# SingleCtrl.net
KiCad netlist of a schematic drawn in EAGLE
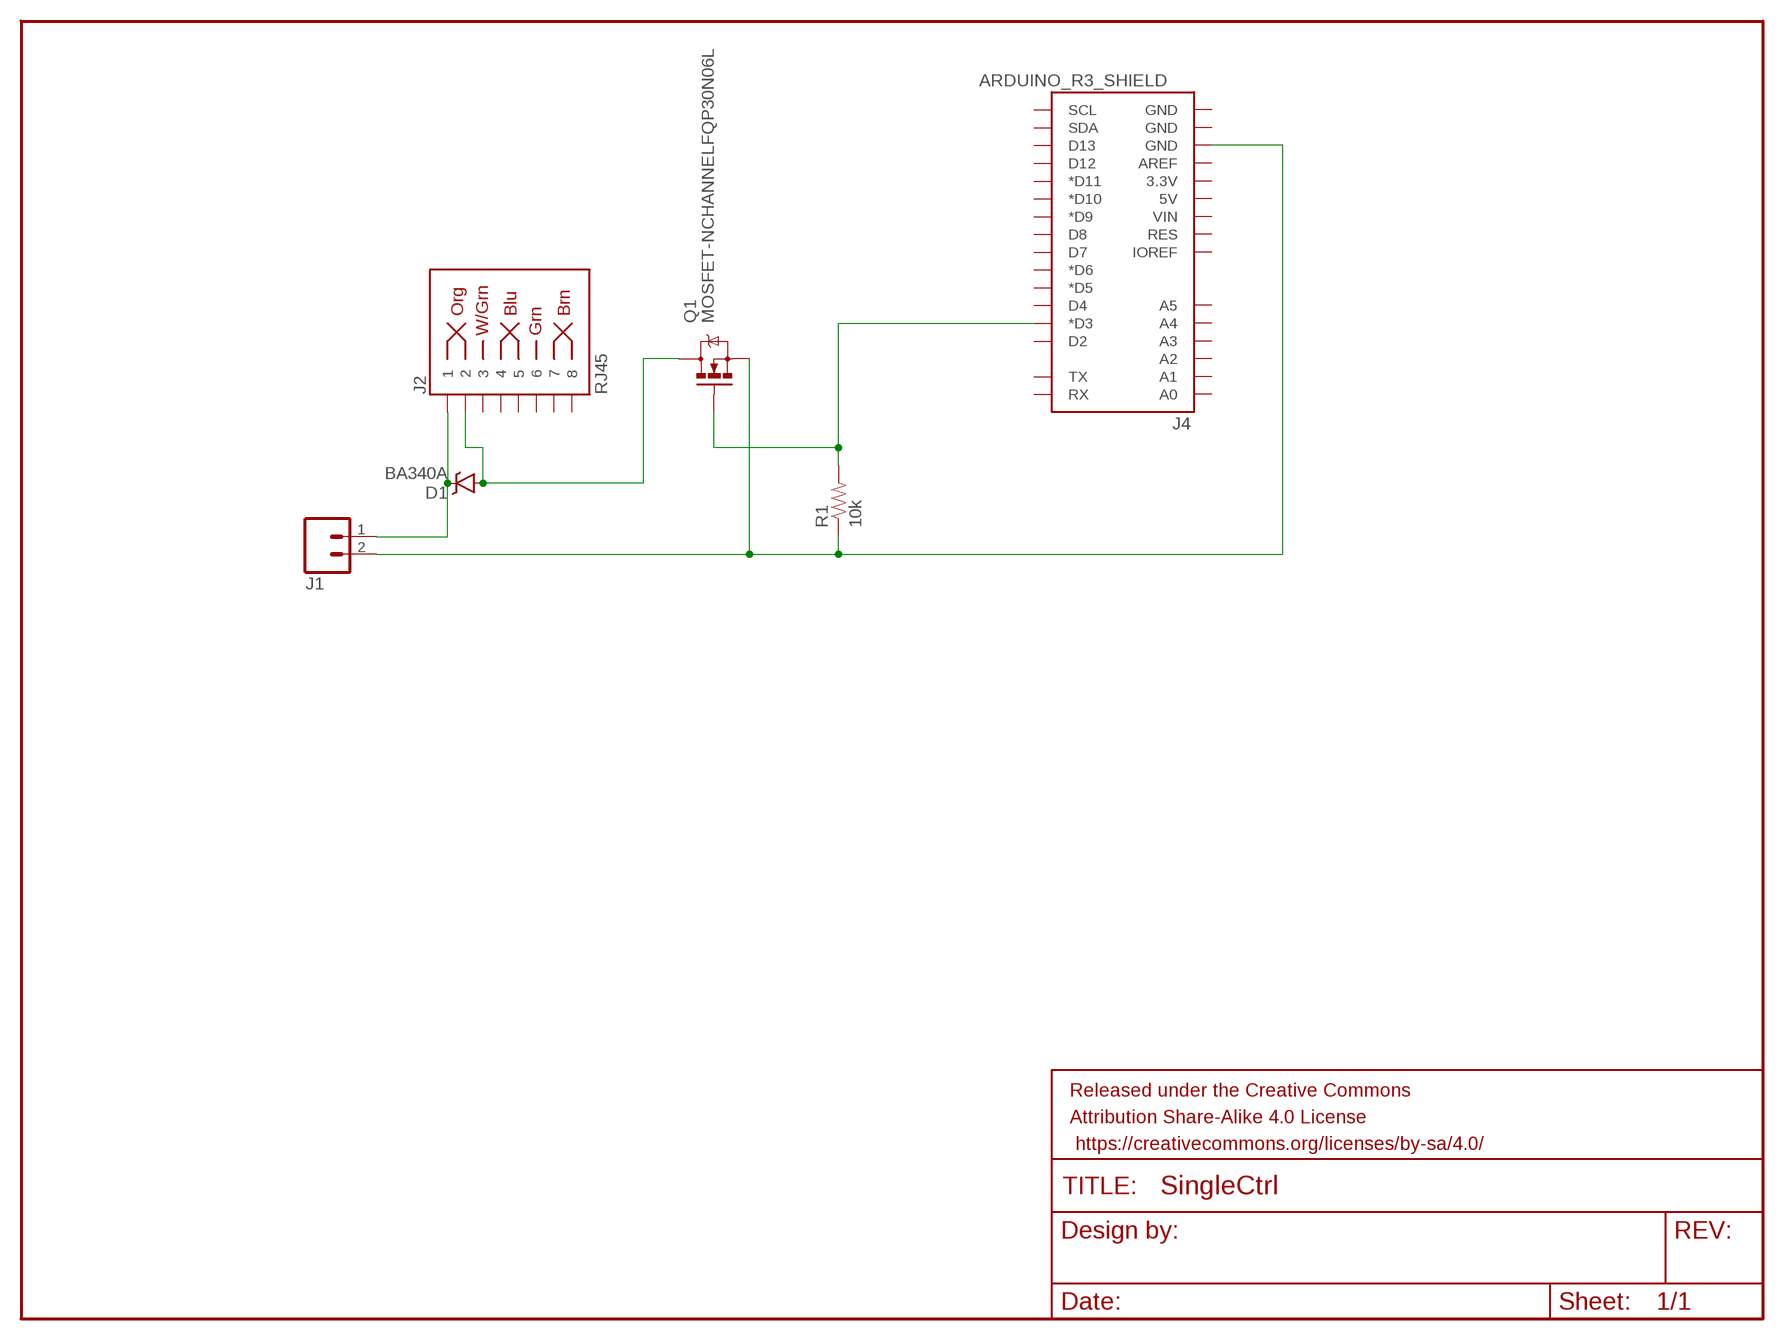
[diagram p0: schematic, sheet 1]

(export (version "E")
  (design (tool "Eeschema 10.0.6"))
  (components
    (comp (ref "D1")
      (value "BA340A")
      (footprint "eagle-import:SMA-DIODE")
      (libsource (lib "eagle-import") (part "B340A"))
    )
    (comp (ref "FRAME1")
      (value "FRAME-LETTER")
      (footprint "eagle-import:CREATIVE_COMMONS")
      (libsource (lib "eagle-import") (part "FRAME-LETTER"))
    )
    (comp (ref "J1")
      (value "M02JST-PTH-2")
      (footprint "eagle-import:JST-2-PTH")
      (libsource (lib "eagle-import") (part "M02JST-PTH-2"))
    )
    (comp (ref "J2")
      (value "RJ45")
      (footprint "eagle-import:RJ45-8")
      (libsource (lib "eagle-import") (part "RJ45-8PTH"))
    )
    (comp (ref "J4")
      (value "ARDUINO_R3_SHIELD")
      (footprint "eagle-import:UNO_R3_SHIELD")
      (libsource (lib "eagle-import") (part "ARDUINO_R3_SHIELD"))
    )
    (comp (ref "Q1")
      (value "MOSFET-NCHANNELFQP30N06L")
      (footprint "eagle-import:TO220V")
      (libsource (lib "eagle-import") (part "MOSFET-NCHANNELFQP30N06L"))
    )
    (comp (ref "R1")
      (value "10k")
      (footprint "eagle-import:AXIAL-0.3")
      (libsource (lib "eagle-import") (part "10KOHM-1/4W-1%(PTH)HORIZ"))
    )
  )
  (nets
    (net (code "1") (name "Net-(D1-PadC)") (class "Default")
      (node (ref "D1") (pin "C") (pinfunction "C_C") (pintype "passive"))
      (node (ref "J1") (pin "1") (pinfunction "1_1") (pintype "passive"))
      (node (ref "J2") (pin "1") (pinfunction "1_1") (pintype "bidirectional"))
    )
    (net (code "2") (name "Net-(J4-*D3)") (class "Default")
      (node (ref "J4") (pin "D3") (pinfunction "*D3_D3") (pintype "bidirectional"))
      (node (ref "Q1") (pin "1") (pinfunction "G_1") (pintype "passive"))
      (node (ref "R1") (pin "P$2") (pinfunction "2_P$2") (pintype "passive"))
    )
    (net (code "3") (name "Net-(Q1-D)") (class "Default")
      (node (ref "D1") (pin "A") (pinfunction "A_A") (pintype "passive"))
      (node (ref "J2") (pin "2") (pinfunction "2_2") (pintype "bidirectional"))
      (node (ref "Q1") (pin "2") (pinfunction "D_2") (pintype "passive"))
    )
    (net (code "4") (name "Net-(Q1-S)") (class "Default")
      (node (ref "J1") (pin "2") (pinfunction "2_2") (pintype "passive"))
      (node (ref "J4") (pin "GND@2") (pinfunction "GND_GND@2") (pintype "bidirectional"))
      (node (ref "Q1") (pin "3") (pinfunction "S_3") (pintype "passive"))
      (node (ref "R1") (pin "P$1") (pinfunction "1_P$1") (pintype "passive"))
    )
    (net (code "5") (name "unconnected-(J2-Pad3)") (class "Default")
      (node (ref "J2") (pin "3") (pinfunction "3_3") (pintype "bidirectional"))
    )
    (net (code "6") (name "unconnected-(J2-Pad4)") (class "Default")
      (node (ref "J2") (pin "4") (pinfunction "4_4") (pintype "bidirectional"))
    )
    (net (code "7") (name "unconnected-(J2-Pad5)") (class "Default")
      (node (ref "J2") (pin "5") (pinfunction "5_5") (pintype "bidirectional"))
    )
    (net (code "8") (name "unconnected-(J2-Pad6)") (class "Default")
      (node (ref "J2") (pin "6") (pinfunction "6_6") (pintype "bidirectional"))
    )
    (net (code "9") (name "unconnected-(J2-Pad7)") (class "Default")
      (node (ref "J2") (pin "7") (pinfunction "7_7") (pintype "bidirectional"))
    )
    (net (code "10") (name "unconnected-(J2-Pad8)") (class "Default")
      (node (ref "J2") (pin "8") (pinfunction "8_8") (pintype "bidirectional"))
    )
    (net (code "11") (name "unconnected-(J4-*D5-PadD5)") (class "Default")
      (node (ref "J4") (pin "D5") (pinfunction "*D5_D5") (pintype "bidirectional"))
    )
    (net (code "12") (name "unconnected-(J4-*D6-PadD6)") (class "Default")
      (node (ref "J4") (pin "D6") (pinfunction "*D6_D6") (pintype "bidirectional"))
    )
    (net (code "13") (name "unconnected-(J4-*D9-PadD9)") (class "Default")
      (node (ref "J4") (pin "D9") (pinfunction "*D9_D9") (pintype "bidirectional"))
    )
    (net (code "14") (name "unconnected-(J4-*D10-PadD10)") (class "Default")
      (node (ref "J4") (pin "D10") (pinfunction "*D10_D10") (pintype "bidirectional"))
    )
    (net (code "15") (name "unconnected-(J4-*D11-PadD11)") (class "Default")
      (node (ref "J4") (pin "D11") (pinfunction "*D11_D11") (pintype "bidirectional"))
    )
    (net (code "16") (name "unconnected-(J4-GND-PadGND@0)") (class "Default")
      (node (ref "J4") (pin "GND@0") (pinfunction "GND_GND@0") (pintype "bidirectional"))
    )
    (net (code "17") (name "unconnected-(J4-GND-PadGND@1)") (class "Default")
      (node (ref "J4") (pin "GND@1") (pinfunction "GND_GND@1") (pintype "bidirectional"))
    )
    (net (code "18") (name "unconnected-(J4-Pad3.3V)") (class "Default")
      (node (ref "J4") (pin "3.3V") (pinfunction "3.3V_3.3V") (pintype "bidirectional"))
    )
    (net (code "19") (name "unconnected-(J4-Pad5V)") (class "Default")
      (node (ref "J4") (pin "5V") (pinfunction "5V_5V") (pintype "bidirectional"))
    )
    (net (code "20") (name "unconnected-(J4-PadA0)") (class "Default")
      (node (ref "J4") (pin "A0") (pinfunction "A0_A0") (pintype "bidirectional"))
    )
    (net (code "21") (name "unconnected-(J4-PadA1)") (class "Default")
      (node (ref "J4") (pin "A1") (pinfunction "A1_A1") (pintype "bidirectional"))
    )
    (net (code "22") (name "unconnected-(J4-PadA2)") (class "Default")
      (node (ref "J4") (pin "A2") (pinfunction "A2_A2") (pintype "bidirectional"))
    )
    (net (code "23") (name "unconnected-(J4-PadA3)") (class "Default")
      (node (ref "J4") (pin "A3") (pinfunction "A3_A3") (pintype "bidirectional"))
    )
    (net (code "24") (name "unconnected-(J4-PadA4)") (class "Default")
      (node (ref "J4") (pin "A4") (pinfunction "A4_A4") (pintype "bidirectional"))
    )
    (net (code "25") (name "unconnected-(J4-PadA5)") (class "Default")
      (node (ref "J4") (pin "A5") (pinfunction "A5_A5") (pintype "bidirectional"))
    )
    (net (code "26") (name "unconnected-(J4-PadAREF)") (class "Default")
      (node (ref "J4") (pin "AREF") (pinfunction "AREF_AREF") (pintype "bidirectional"))
    )
    (net (code "27") (name "unconnected-(J4-PadD2)") (class "Default")
      (node (ref "J4") (pin "D2") (pinfunction "D2_D2") (pintype "bidirectional"))
    )
    (net (code "28") (name "unconnected-(J4-PadD4)") (class "Default")
      (node (ref "J4") (pin "D4") (pinfunction "D4_D4") (pintype "bidirectional"))
    )
    (net (code "29") (name "unconnected-(J4-PadD7)") (class "Default")
      (node (ref "J4") (pin "D7") (pinfunction "D7_D7") (pintype "bidirectional"))
    )
    (net (code "30") (name "unconnected-(J4-PadD8)") (class "Default")
      (node (ref "J4") (pin "D8") (pinfunction "D8_D8") (pintype "bidirectional"))
    )
    (net (code "31") (name "unconnected-(J4-PadD12)") (class "Default")
      (node (ref "J4") (pin "D12") (pinfunction "D12_D12") (pintype "bidirectional"))
    )
    (net (code "32") (name "unconnected-(J4-PadD13)") (class "Default")
      (node (ref "J4") (pin "D13") (pinfunction "D13_D13") (pintype "bidirectional"))
    )
    (net (code "33") (name "unconnected-(J4-PadIOREF)") (class "Default")
      (node (ref "J4") (pin "IOREF") (pinfunction "IOREF_IOREF") (pintype "bidirectional"))
    )
    (net (code "34") (name "unconnected-(J4-PadRES)") (class "Default")
      (node (ref "J4") (pin "RES") (pinfunction "RES_RES") (pintype "bidirectional"))
    )
    (net (code "35") (name "unconnected-(J4-PadRX)") (class "Default")
      (node (ref "J4") (pin "RX") (pinfunction "RX_RX") (pintype "bidirectional"))
    )
    (net (code "36") (name "unconnected-(J4-PadSCL)") (class "Default")
      (node (ref "J4") (pin "SCL") (pinfunction "SCL_SCL") (pintype "bidirectional"))
    )
    (net (code "37") (name "unconnected-(J4-PadSDA)") (class "Default")
      (node (ref "J4") (pin "SDA") (pinfunction "SDA_SDA") (pintype "bidirectional"))
    )
    (net (code "38") (name "unconnected-(J4-PadTX)") (class "Default")
      (node (ref "J4") (pin "TX") (pinfunction "TX_TX") (pintype "bidirectional"))
    )
    (net (code "39") (name "unconnected-(J4-PadVIN)") (class "Default")
      (node (ref "J4") (pin "VIN") (pinfunction "VIN_VIN") (pintype "bidirectional"))
    )
  )
)
